# Fonte_5.net
KiCad netlist of a schematic drawn in Altium Designer
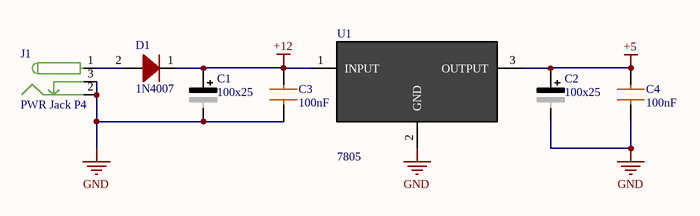
[diagram p0: Fonte +5.SchDoc]

(export (version "E")
  (design (tool "Eeschema 10.0.6"))
  (components
    (comp (ref "C1")
      (value "100x25")
      (footprint "CAP 100X25 SMD")
      (description "Polarized Capacitor (Radial)")
      (fields (field (name "PUBLISHER") "Altium Limited"))
      (libsource (lib "Gerenciador de abastecimento") (part "CAPACITOR ELETROLITICO"))
    )
    (comp (ref "C2")
      (value "100x25")
      (footprint "CAP 100X25 SMD")
      (description "Polarized Capacitor (Radial)")
      (fields (field (name "PUBLISHER") "Altium Limited"))
      (libsource (lib "Gerenciador de abastecimento") (part "CAPACITOR ELETROLITICO"))
    )
    (comp (ref "C3")
      (value "100nF")
      (footprint "Capacitor 0805")
      (description "Capacitor")
      (fields (field (name "PUBLISHER") "Altium Limited"))
      (libsource (lib "Gerenciador de abastecimento") (part "CAPACITOR"))
    )
    (comp (ref "C4")
      (value "100nF")
      (footprint "Capacitor 0805")
      (description "Capacitor")
      (fields (field (name "PUBLISHER") "Altium Limited"))
      (libsource (lib "Gerenciador de abastecimento") (part "CAPACITOR"))
    )
    (comp (ref "D1")
      (value "1N4007")
      (footprint "SOD123")
      (description "Diodo retificador de uso geral.")
      (fields (field (name "PUBLISHER") "Altium Limited"))
      (libsource (lib "Gerenciador de abastecimento") (part "DIODO 1N4007"))
    )
    (comp (ref "J1")
      (value "PWR Jack P4")
      (footprint "Jack P4 SMT")
      (description "Connector Power PL 2 POS Solder RA Thru-Hole 3 Terminal 1 Port Bulk")
      (fields
        (field (name "MANUFACTURER") "Switchcraft")
        (field (name "MANUFACTURER PART NUMBER") "RAPC712X")
      )
      (libsource (lib "Gerenciador de abastecimento") (part "PWR Jack P4"))
    )
    (comp (ref "U1")
      (value "7805")
      (footprint "TO252-3")
      (libsource (lib "Gerenciador de abastecimento") (part "L7805"))
    )
  )
  (nets
    (net (code "1") (name "+5") (class "Default")
      (node (ref "C2") (pin "1") (pinfunction "+_1") (pintype "passive"))
      (node (ref "C4") (pin "2") (pinfunction "2_2") (pintype "passive"))
      (node (ref "U1") (pin "3") (pinfunction "OUTPUT_3") (pintype "passive"))
    )
    (net (code "2") (name "+12") (class "Default")
      (node (ref "C1") (pin "1") (pinfunction "+_1") (pintype "passive"))
      (node (ref "C3") (pin "2") (pinfunction "2_2") (pintype "passive"))
      (node (ref "D1") (pin "1") (pinfunction "1_1") (pintype "passive"))
      (node (ref "U1") (pin "1") (pinfunction "INPUT_1") (pintype "passive"))
    )
    (net (code "3") (name "GND") (class "Default")
      (node (ref "C1") (pin "2") (pinfunction "-_2") (pintype "passive"))
      (node (ref "C2") (pin "2") (pinfunction "-_2") (pintype "passive"))
      (node (ref "C3") (pin "1") (pinfunction "1_1") (pintype "passive"))
      (node (ref "C4") (pin "1") (pinfunction "1_1") (pintype "passive"))
      (node (ref "J1") (pin "2") (pinfunction "2_2") (pintype "passive"))
      (node (ref "J1") (pin "3") (pinfunction "3_3") (pintype "passive"))
      (node (ref "U1") (pin "2") (pinfunction "GND_2") (pintype "passive"))
    )
    (net (code "4") (name "Net-(D1-Pad2)") (class "Default")
      (node (ref "D1") (pin "2") (pinfunction "2_2") (pintype "passive"))
      (node (ref "J1") (pin "1") (pinfunction "1_1") (pintype "passive"))
    )
  )
)
